# EVK-IRIS-W1-MUCLINK.net
KiCad netlist of a schematic drawn in Altium Designer
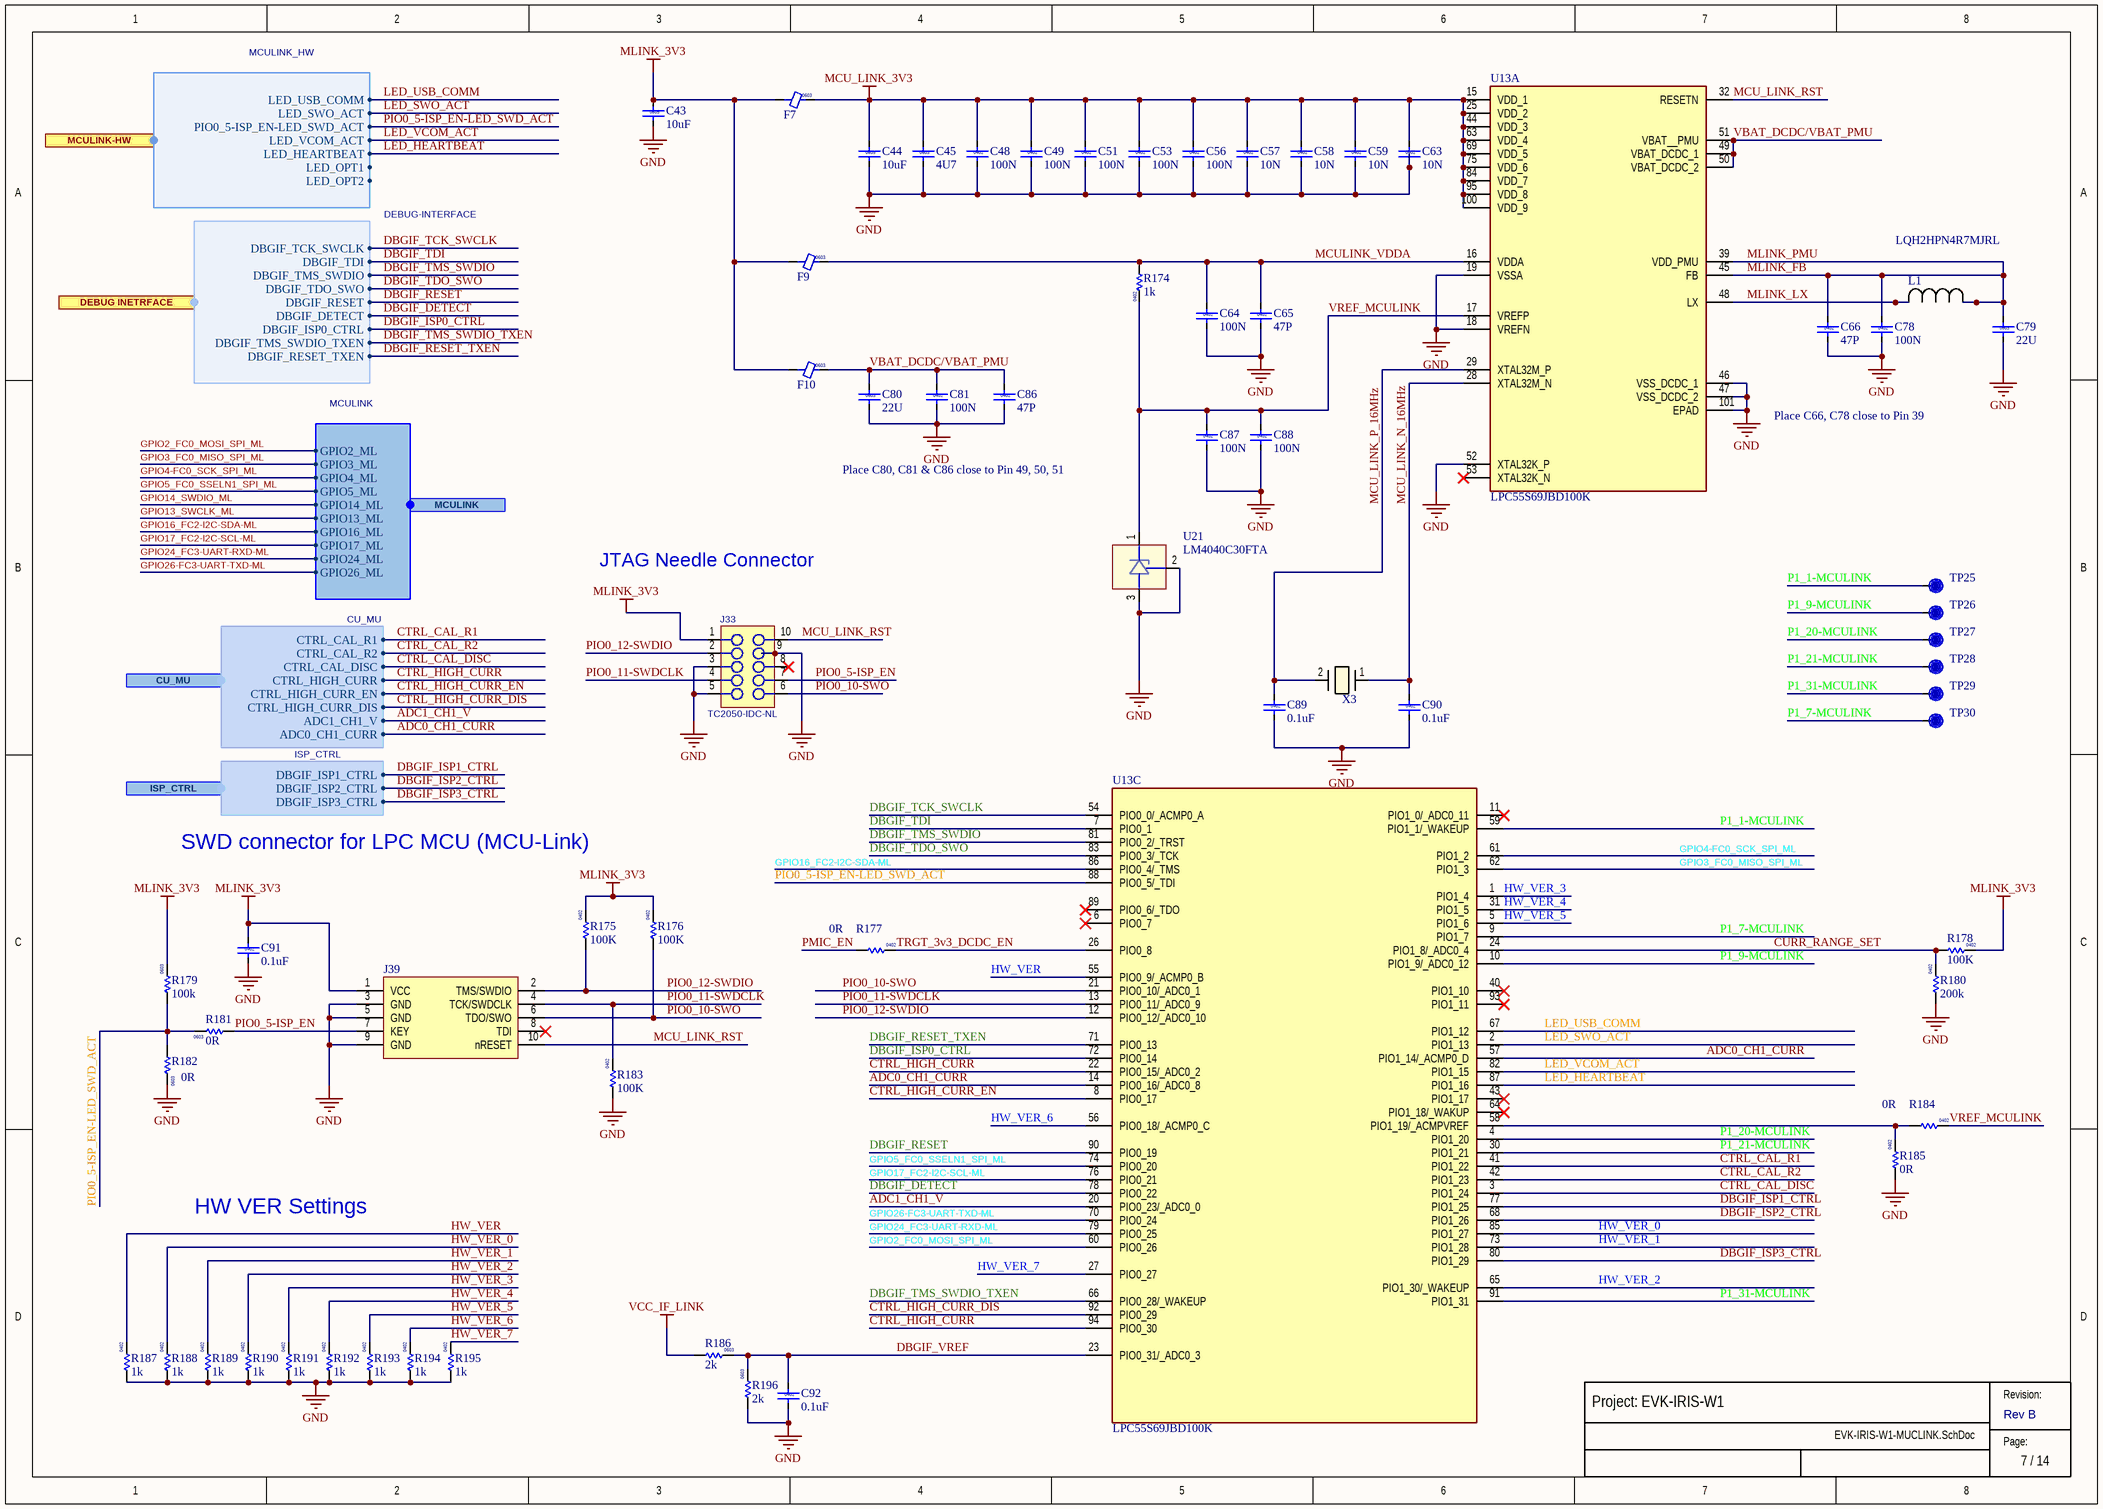
[diagram p0: EVK-IRIS-W1-MUCLINK.SchDoc]

(export (version "E")
  (design (tool "Eeschema 10.0.6"))
  (components
    (comp (ref "C43")
      (value "10uF")
      (footprint "Cap 0805 HD")
      (description "CAP CER 10uF 25V 10% X5R 0805")
      (fields
        (field (name "SIZE") "0805")
        (field (name "PART NUMBER") "120-00129")
        (field (name "TOLERANCE") "+/- 10%")
      )
      (libsource (lib "Arena_Parts_DB_Lib") (part "Cap Chip"))
    )
    (comp (ref "C44")
      (value "10uF")
      (footprint "Cap 0805 HD")
      (description "CAP CER 10uF 25V 10% X5R 0805")
      (fields
        (field (name "SIZE") "0805")
        (field (name "PART NUMBER") "120-00129")
        (field (name "TOLERANCE") "+/- 10%")
      )
      (libsource (lib "Arena_Parts_DB_Lib") (part "Cap Chip"))
    )
    (comp (ref "C45")
      (value "4U7")
      (footprint "Cap 0603 HD")
      (description "CAP CER X6S 0603 AUTOMOTIVE 4U7 10%")
      (fields
        (field (name "SIZE") "0603")
        (field (name "PART NUMBER") "UBXH01-0000278")
        (field (name "TOLERANCE") "10%")
        (field (name "EDITOR") "philippe.largier")
        (field (name "RELEASED BY") "alvaro.nussbaum")
      )
      (libsource (lib "UBX_Parts_DB_Lib") (part "Cap Chip"))
    )
    (comp (ref "C48")
      (value "100N")
      (footprint "Cap_0402_1100Lx600Wx600H_600x600Pad_350G_FLX")
      (description "CAP CER X7R 0402 100N 10% 16V")
      (fields
        (field (name "SIZE") "0402")
        (field (name "PART NUMBER") "UBXH01-0000233")
        (field (name "TOLERANCE") "10%")
        (field (name "EDITOR") "philippe.largier")
        (field (name "RELEASED BY") "charlotte.biber")
      )
      (libsource (lib "UBX_Parts_DB_Lib") (part "Cap Chip"))
    )
    (comp (ref "C49")
      (value "100N")
      (footprint "Cap_0402_1100Lx600Wx600H_600x600Pad_350G_FLX")
      (description "CAP CER X7R 0402 100N 10% 16V")
      (fields
        (field (name "SIZE") "0402")
        (field (name "PART NUMBER") "UBXH01-0000233")
        (field (name "TOLERANCE") "10%")
        (field (name "EDITOR") "philippe.largier")
        (field (name "RELEASED BY") "charlotte.biber")
      )
      (libsource (lib "UBX_Parts_DB_Lib") (part "Cap Chip"))
    )
    (comp (ref "C51")
      (value "100N")
      (footprint "Cap_0402_1100Lx600Wx600H_600x600Pad_350G_FLX")
      (description "CAP CER X7R 0402 100N 10% 16V")
      (fields
        (field (name "SIZE") "0402")
        (field (name "PART NUMBER") "UBXH01-0000233")
        (field (name "TOLERANCE") "10%")
        (field (name "EDITOR") "philippe.largier")
        (field (name "RELEASED BY") "charlotte.biber")
      )
      (libsource (lib "UBX_Parts_DB_Lib") (part "Cap Chip"))
    )
    (comp (ref "C53")
      (value "100N")
      (footprint "Cap_0402_1100Lx600Wx600H_600x600Pad_350G_FLX")
      (description "CAP CER X7R 0402 100N 10% 16V")
      (fields
        (field (name "SIZE") "0402")
        (field (name "PART NUMBER") "UBXH01-0000233")
        (field (name "TOLERANCE") "10%")
        (field (name "EDITOR") "philippe.largier")
        (field (name "RELEASED BY") "charlotte.biber")
      )
      (libsource (lib "UBX_Parts_DB_Lib") (part "Cap Chip"))
    )
    (comp (ref "C56")
      (value "100N")
      (footprint "Cap_0402_1100Lx600Wx600H_600x600Pad_350G_FLX")
      (description "CAP CER X7R 0402 100N 10% 16V")
      (fields
        (field (name "SIZE") "0402")
        (field (name "PART NUMBER") "UBXH01-0000233")
        (field (name "TOLERANCE") "10%")
        (field (name "EDITOR") "philippe.largier")
        (field (name "RELEASED BY") "charlotte.biber")
      )
      (libsource (lib "UBX_Parts_DB_Lib") (part "Cap Chip"))
    )
    (comp (ref "C57")
      (value "10N")
      (footprint "Cap_0402_1100Lx600Wx600H_600x600Pad_350G_FLX")
      (description "CAP CER X7R 0402 10N 10% 16V")
      (fields
        (field (name "SIZE") "0402")
        (field (name "PART NUMBER") "UBXH01-0023025")
        (field (name "TOLERANCE") "10%")
        (field (name "EDITOR") "roland.rust")
        (field (name "RELEASED BY") "anthony.gergis")
      )
      (libsource (lib "UBX_Parts_DB_Lib") (part "Cap Chip"))
    )
    (comp (ref "C58")
      (value "10N")
      (footprint "Cap_0402_1100Lx600Wx600H_600x600Pad_350G_FLX")
      (description "CAP CER X7R 0402 10N 10% 16V")
      (fields
        (field (name "SIZE") "0402")
        (field (name "PART NUMBER") "UBXH01-0023025")
        (field (name "TOLERANCE") "10%")
        (field (name "EDITOR") "roland.rust")
        (field (name "RELEASED BY") "anthony.gergis")
      )
      (libsource (lib "UBX_Parts_DB_Lib") (part "Cap Chip"))
    )
    (comp (ref "C59")
      (value "10N")
      (footprint "Cap_0402_1100Lx600Wx600H_600x600Pad_350G_FLX")
      (description "CAP CER X7R 0402 10N 10% 16V")
      (fields
        (field (name "SIZE") "0402")
        (field (name "PART NUMBER") "UBXH01-0023025")
        (field (name "TOLERANCE") "10%")
        (field (name "EDITOR") "roland.rust")
        (field (name "RELEASED BY") "anthony.gergis")
      )
      (libsource (lib "UBX_Parts_DB_Lib") (part "Cap Chip"))
    )
    (comp (ref "C63")
      (value "10N")
      (footprint "Cap_0402_1100Lx600Wx600H_600x600Pad_350G_FLX")
      (description "CAP CER X7R 0402 10N 10% 16V")
      (fields
        (field (name "SIZE") "0402")
        (field (name "PART NUMBER") "UBXH01-0023025")
        (field (name "TOLERANCE") "10%")
        (field (name "EDITOR") "roland.rust")
        (field (name "RELEASED BY") "anthony.gergis")
      )
      (libsource (lib "UBX_Parts_DB_Lib") (part "Cap Chip"))
    )
    (comp (ref "C64")
      (value "100N")
      (footprint "Cap_0402_1100Lx600Wx600H_600x600Pad_350G_FLX")
      (description "CAP CER X7R 0402 100N 10% 16V")
      (fields
        (field (name "SIZE") "0402")
        (field (name "PART NUMBER") "UBXH01-0000233")
        (field (name "TOLERANCE") "10%")
        (field (name "EDITOR") "philippe.largier")
        (field (name "RELEASED BY") "charlotte.biber")
      )
      (libsource (lib "UBX_Parts_DB_Lib") (part "Cap Chip"))
    )
    (comp (ref "C65")
      (value "47P")
      (footprint "Cap_0402_1100Lx600Wx600H_600x600Pad_350G_FLX")
      (description "CAP CER C0G 0402 47P 10% 25V")
      (fields
        (field (name "SIZE") "0402")
        (field (name "PART NUMBER") "UBXH01-0008022")
        (field (name "TOLERANCE") "10%")
        (field (name "EDITOR") "andreas.thiel")
      )
      (libsource (lib "UBX_Parts_DB_Lib") (part "Cap Chip"))
    )
    (comp (ref "C66")
      (value "47P")
      (footprint "Cap_0402_1100Lx600Wx600H_600x600Pad_350G_FLX")
      (description "CAP CER C0G 0402 47P 10% 25V")
      (fields
        (field (name "SIZE") "0402")
        (field (name "PART NUMBER") "UBXH01-0008022")
        (field (name "TOLERANCE") "10%")
        (field (name "EDITOR") "andreas.thiel")
      )
      (libsource (lib "UBX_Parts_DB_Lib") (part "Cap Chip"))
    )
    (comp (ref "C78")
      (value "100N")
      (footprint "Cap_0402_1100Lx600Wx600H_600x600Pad_350G_FLX")
      (description "CAP CER X7R 0402 100N 10% 16V")
      (fields
        (field (name "SIZE") "0402")
        (field (name "PART NUMBER") "UBXH01-0000233")
        (field (name "TOLERANCE") "10%")
        (field (name "EDITOR") "philippe.largier")
        (field (name "RELEASED BY") "charlotte.biber")
      )
      (libsource (lib "UBX_Parts_DB_Lib") (part "Cap Chip"))
    )
    (comp (ref "C79")
      (value "22U")
      (footprint "Cap 0603")
      (description "CAP CER X5R 0603 22U 20% 10V")
      (fields
        (field (name "SIZE") "0603")
        (field (name "PART NUMBER") "UBXH01-0000150")
        (field (name "TOLERANCE") "20%")
        (field (name "EDITOR") "dario.antonaz")
        (field (name "RELEASED BY") "pasquale.scorca")
      )
      (libsource (lib "UBX_Parts_DB_Lib") (part "Cap Chip"))
    )
    (comp (ref "C80")
      (value "22U")
      (footprint "Cap 0603")
      (description "CAP CER X5R 0603 22U 20% 10V")
      (fields
        (field (name "SIZE") "0603")
        (field (name "PART NUMBER") "UBXH01-0000150")
        (field (name "TOLERANCE") "20%")
        (field (name "EDITOR") "dario.antonaz")
        (field (name "RELEASED BY") "pasquale.scorca")
      )
      (libsource (lib "UBX_Parts_DB_Lib") (part "Cap Chip"))
    )
    (comp (ref "C81")
      (value "100N")
      (footprint "Cap_0402_1100Lx600Wx600H_600x600Pad_350G_FLX")
      (description "CAP CER X7R 0402 100N 10% 16V")
      (fields
        (field (name "SIZE") "0402")
        (field (name "PART NUMBER") "UBXH01-0000233")
        (field (name "TOLERANCE") "10%")
        (field (name "EDITOR") "philippe.largier")
        (field (name "RELEASED BY") "charlotte.biber")
      )
      (libsource (lib "UBX_Parts_DB_Lib") (part "Cap Chip"))
    )
    (comp (ref "C86")
      (value "47P")
      (footprint "Cap_0402_1100Lx600Wx600H_600x600Pad_350G_FLX")
      (description "CAP CER C0G 0402 47P 10% 25V")
      (fields
        (field (name "SIZE") "0402")
        (field (name "PART NUMBER") "UBXH01-0008022")
        (field (name "TOLERANCE") "10%")
        (field (name "EDITOR") "andreas.thiel")
      )
      (libsource (lib "UBX_Parts_DB_Lib") (part "Cap Chip"))
    )
    (comp (ref "C87")
      (value "100N")
      (footprint "Cap_0402_1100Lx600Wx600H_600x600Pad_350G_FLX")
      (description "CAP CER X7R 0402 100N 10% 16V")
      (fields
        (field (name "SIZE") "0402")
        (field (name "PART NUMBER") "UBXH01-0000233")
        (field (name "TOLERANCE") "10%")
        (field (name "EDITOR") "philippe.largier")
        (field (name "RELEASED BY") "charlotte.biber")
      )
      (libsource (lib "UBX_Parts_DB_Lib") (part "Cap Chip"))
    )
    (comp (ref "C88")
      (value "100N")
      (footprint "Cap_0402_1100Lx600Wx600H_600x600Pad_350G_FLX")
      (description "CAP CER X7R 0402 100N 10% 16V")
      (fields
        (field (name "SIZE") "0402")
        (field (name "PART NUMBER") "UBXH01-0000233")
        (field (name "TOLERANCE") "10%")
        (field (name "EDITOR") "philippe.largier")
        (field (name "RELEASED BY") "charlotte.biber")
      )
      (libsource (lib "UBX_Parts_DB_Lib") (part "Cap Chip"))
    )
    (comp (ref "C89")
      (value "0.1uF")
      (footprint "Cap 0402 HD")
      (description "Cap, Ceramic 0.1uF 10V 10% X5R 0402")
      (fields
        (field (name "SIZE") "0402")
        (field (name "PART NUMBER") "120-00016")
        (field (name "TOLERANCE") "+/- 10%")
      )
      (libsource (lib "Arena_Parts_DB_Lib") (part "Cap Chip"))
    )
    (comp (ref "C90")
      (value "0.1uF")
      (footprint "Cap 0402 HD")
      (description "Cap, Ceramic 0.1uF 10V 10% X5R 0402")
      (fields
        (field (name "SIZE") "0402")
        (field (name "PART NUMBER") "120-00016")
        (field (name "TOLERANCE") "+/- 10%")
      )
      (libsource (lib "Arena_Parts_DB_Lib") (part "Cap Chip"))
    )
    (comp (ref "C91")
      (value "0.1uF")
      (footprint "Cap 0402 HD")
      (description "Cap, Ceramic 0.1uF 10V 10% X5R 0402")
      (fields
        (field (name "SIZE") "0402")
        (field (name "PART NUMBER") "120-00016")
        (field (name "TOLERANCE") "+/- 10%")
      )
      (libsource (lib "Arena_Parts_DB_Lib") (part "Cap Chip"))
    )
    (comp (ref "C92")
      (value "0.1uF")
      (footprint "Cap 0402 HD")
      (description "Cap, Ceramic 0.1uF 10V 10% X5R 0402")
      (fields
        (field (name "SIZE") "0402")
        (field (name "PART NUMBER") "120-00016")
        (field (name "TOLERANCE") "+/- 10%")
      )
      (libsource (lib "Arena_Parts_DB_Lib") (part "Cap Chip"))
    )
    (comp (ref "F7")
      (value "UBXH08-0041002")
      (footprint "IND 0603")
      (description "FERRITE BEAD MURATA BLM18HD 0603 600R@100MHZ")
      (fields
        (field (name "SIZE") "0603")
        (field (name "MANUFACTURER") "Murata Manufacturing Company, Ltd.")
        (field (name "EDITOR") "roland.rust")
        (field (name "RELEASED BY") "roland.rust")
      )
      (libsource (lib "UBX_Parts_DB_Lib") (part "FB sm"))
    )
    (comp (ref "F9")
      (value "UBXH08-0041002")
      (footprint "IND 0603")
      (description "FERRITE BEAD MURATA BLM18HD 0603 600R@100MHZ")
      (fields
        (field (name "SIZE") "0603")
        (field (name "MANUFACTURER") "Murata Manufacturing Company, Ltd.")
        (field (name "EDITOR") "roland.rust")
        (field (name "RELEASED BY") "roland.rust")
      )
      (libsource (lib "UBX_Parts_DB_Lib") (part "FB sm"))
    )
    (comp (ref "F10")
      (value "UBXH08-0041002")
      (footprint "IND 0603")
      (description "FERRITE BEAD MURATA BLM18HD 0603 600R@100MHZ")
      (fields
        (field (name "SIZE") "0603")
        (field (name "MANUFACTURER") "Murata Manufacturing Company, Ltd.")
        (field (name "EDITOR") "roland.rust")
        (field (name "RELEASED BY") "roland.rust")
      )
      (libsource (lib "UBX_Parts_DB_Lib") (part "FB sm"))
    )
    (comp (ref "J33")
      (value "TC2050-IDC-NLDNP")
      (footprint "TC2050-IDC-NL")
      (description "CON PADS FOR CBL PLUG-OF-NAILS 10-PIN NO LEGS")
      (fields
        (field (name "MANUFACTURER P/N") "TC2050-IDC-NL")
        (field (name "PART NUMBER") "TC2050-IDC-NL")
        (field (name "MANUFACTURER") "TAG Connect")
        (field (name "ADDED BY") "Paul B")
      )
      (libsource (lib "LEGACY_Rigado_AltiumLib") (part "CON-10Pin_2Row_ALT"))
    )
    (comp (ref "J39")
      (value "130-00099")
      (footprint "HDR.050P-10Pin-2x5-SMT_Key")
      (description "Header 0.05\" 10Pin 2Row SMD Black")
      (fields (field (name "VOLTAGE") "None"))
      (libsource (lib "Arena_Parts_DB_Lib") (part "JTAG-10Pin"))
    )
    (comp (ref "L1")
      (value "LQH2HPN4R7MJRL")
      (footprint "IND_LQH2HPN4R7MJRL_MUR")
      (description "No Description Available")
      (fields (field (name "COPYRIGHT") "Copyright (C) 2023 Ultra Librarian. All rights reserved."))
      (libsource (lib "LQH2HPN4R7MJRL") (part "LQH2HPN4R7MJRL"))
    )
    (comp (ref "R174")
      (value "1k")
      (footprint "RES 0402 HD")
      (description "Resistor 1k ohm 1% 1/16W, 0402")
      (fields
        (field (name "SIZE") "0402")
        (field (name "PART NUMBER") "180-00021")
        (field (name "POWER") "1/16W")
      )
      (libsource (lib "Arena_Parts_DB_Lib") (part "Res sm"))
    )
    (comp (ref "R175")
      (value "100K")
      (footprint "RES 0402 HD")
      (description "RES THICK FILM CHIP 0402 100K 1% 63mW")
      (fields
        (field (name "SIZE") "0402")
        (field (name "PART NUMBER") "UBXH18-0000005")
        (field (name "TOLERANCE") "1%")
        (field (name "EDITOR") "dario.antonaz")
        (field (name "RELEASED BY") "sandro.sestan")
      )
      (libsource (lib "UBX_Parts_DB_Lib") (part "Res sm"))
    )
    (comp (ref "R176")
      (value "100K")
      (footprint "RES 0402 HD")
      (description "RES THICK FILM CHIP 0402 100K 1% 63mW")
      (fields
        (field (name "SIZE") "0402")
        (field (name "PART NUMBER") "UBXH18-0000005")
        (field (name "TOLERANCE") "1%")
        (field (name "EDITOR") "dario.antonaz")
        (field (name "RELEASED BY") "sandro.sestan")
      )
      (libsource (lib "UBX_Parts_DB_Lib") (part "Res sm"))
    )
    (comp (ref "R177")
      (value "0R")
      (footprint "RES 0402 HD")
      (description "RES THICK FILM CHIP 0402 0R 0 100mW")
      (fields
        (field (name "SIZE") "0402")
        (field (name "PART NUMBER") "UBXH18-0003002")
        (field (name "TOLERANCE") "0")
        (field (name "EDITOR") "charlotte.biber")
        (field (name "RELEASED BY") "peter.mueller")
      )
      (libsource (lib "UBX_Parts_DB_Lib") (part "Res sm"))
    )
    (comp (ref "R178")
      (value "100K")
      (footprint "RES 0402 HD")
      (description "RES THICK FILM CHIP 0402 100K 1% 63mW")
      (fields
        (field (name "SIZE") "0402")
        (field (name "PART NUMBER") "UBXH18-0000005")
        (field (name "TOLERANCE") "1%")
        (field (name "EDITOR") "dario.antonaz")
        (field (name "RELEASED BY") "sandro.sestan")
      )
      (libsource (lib "UBX_Parts_DB_Lib") (part "Res sm"))
    )
    (comp (ref "R179")
      (value "100k")
      (footprint "RES 0603 HD")
      (description "Resistor, 100k ohm 1% 1/10W, 0603")
      (fields
        (field (name "SIZE") "0603")
        (field (name "PART NUMBER") "180-00014")
        (field (name "POWER") "1/10W")
      )
      (libsource (lib "Arena_Parts_DB_Lib") (part "Res sm"))
    )
    (comp (ref "R180")
      (value "200k")
      (footprint "RES 0402 HD")
      (description "Resistor 200k ohm 1%, 1/16W, 0402")
      (fields
        (field (name "SIZE") "0402")
        (field (name "PART NUMBER") "180-00055")
        (field (name "POWER") "1/16W")
      )
      (libsource (lib "Arena_Parts_DB_Lib") (part "Res sm"))
    )
    (comp (ref "R181")
      (value "0R")
      (footprint "RES 0603 HD")
      (description "RES THICK FILM CHIP 0603 0R 0 100mW")
      (fields
        (field (name "SIZE") "0603")
        (field (name "PART NUMBER") "UBXH18-0003001")
        (field (name "TOLERANCE") "0")
        (field (name "EDITOR") "martin.frauchiger")
        (field (name "RELEASED BY") "martin.frauchiger")
      )
      (libsource (lib "UBX_Parts_DB_Lib") (part "Res sm"))
    )
    (comp (ref "R182")
      (value "0R")
      (footprint "RES 0603 HD")
      (description "Resistor 0 ohm Jumper, 1/10W, 0603")
      (fields
        (field (name "SIZE") "0603")
        (field (name "PART NUMBER") "180-00012")
        (field (name "POWER") "1/10W")
      )
      (libsource (lib "Arena_Parts_DB_Lib") (part "Res sm"))
    )
    (comp (ref "R183")
      (value "100K")
      (footprint "RES 0402 HD")
      (description "RES THICK FILM CHIP 0402 100K 1% 63mW")
      (fields
        (field (name "SIZE") "0402")
        (field (name "PART NUMBER") "UBXH18-0000005")
        (field (name "TOLERANCE") "1%")
        (field (name "EDITOR") "dario.antonaz")
        (field (name "RELEASED BY") "sandro.sestan")
      )
      (libsource (lib "UBX_Parts_DB_Lib") (part "Res sm"))
    )
    (comp (ref "R184")
      (value "0R")
      (footprint "RES 0402 HD")
      (description "RES THICK FILM CHIP 0402 0R 0 100mW")
      (fields
        (field (name "SIZE") "0402")
        (field (name "PART NUMBER") "UBXH18-0003002")
        (field (name "TOLERANCE") "0")
        (field (name "EDITOR") "charlotte.biber")
        (field (name "RELEASED BY") "peter.mueller")
      )
      (libsource (lib "UBX_Parts_DB_Lib") (part "Res sm"))
    )
    (comp (ref "R185")
      (value "0R")
      (footprint "RES 0402 HD")
      (description "RES THICK FILM CHIP 0402 0R 0 100mW")
      (fields
        (field (name "SIZE") "0402")
        (field (name "PART NUMBER") "UBXH18-0003002")
        (field (name "TOLERANCE") "0")
        (field (name "EDITOR") "charlotte.biber")
        (field (name "RELEASED BY") "peter.mueller")
      )
      (libsource (lib "UBX_Parts_DB_Lib") (part "Res sm"))
    )
    (comp (ref "R186")
      (value "2k")
      (footprint "RES 0603 HD")
      (description "Resistor 2k ohm 1% 1/10W, 0603.")
      (fields
        (field (name "SIZE") "0603")
        (field (name "PART NUMBER") "180-00037")
        (field (name "POWER") "1/10W")
      )
      (libsource (lib "Arena_Parts_DB_Lib") (part "Res sm"))
    )
    (comp (ref "R187")
      (value "1k")
      (footprint "RES 0402 HD")
      (description "Resistor 1k ohm 1% 1/16W, 0402")
      (fields
        (field (name "SIZE") "0402")
        (field (name "PART NUMBER") "180-00021")
        (field (name "POWER") "1/16W")
      )
      (libsource (lib "Arena_Parts_DB_Lib") (part "Res sm"))
    )
    (comp (ref "R188")
      (value "1k")
      (footprint "RES 0402 HD")
      (description "Resistor 1k ohm 1% 1/16W, 0402")
      (fields
        (field (name "SIZE") "0402")
        (field (name "PART NUMBER") "180-00021")
        (field (name "POWER") "1/16W")
      )
      (libsource (lib "Arena_Parts_DB_Lib") (part "Res sm"))
    )
    (comp (ref "R189")
      (value "1k")
      (footprint "RES 0402 HD")
      (description "Resistor 1k ohm 1% 1/16W, 0402")
      (fields
        (field (name "SIZE") "0402")
        (field (name "PART NUMBER") "180-00021")
        (field (name "POWER") "1/16W")
      )
      (libsource (lib "Arena_Parts_DB_Lib") (part "Res sm"))
    )
    (comp (ref "R190")
      (value "1k")
      (footprint "RES 0402 HD")
      (description "Resistor 1k ohm 1% 1/16W, 0402")
      (fields
        (field (name "SIZE") "0402")
        (field (name "PART NUMBER") "180-00021")
        (field (name "POWER") "1/16W")
      )
      (libsource (lib "Arena_Parts_DB_Lib") (part "Res sm"))
    )
    (comp (ref "R191")
      (value "1k")
      (footprint "RES 0402 HD")
      (description "Resistor 1k ohm 1% 1/16W, 0402")
      (fields
        (field (name "SIZE") "0402")
        (field (name "PART NUMBER") "180-00021")
        (field (name "POWER") "1/16W")
      )
      (libsource (lib "Arena_Parts_DB_Lib") (part "Res sm"))
    )
    (comp (ref "R192")
      (value "1k")
      (footprint "RES 0402 HD")
      (description "Resistor 1k ohm 1% 1/16W, 0402")
      (fields
        (field (name "SIZE") "0402")
        (field (name "PART NUMBER") "180-00021")
        (field (name "POWER") "1/16W")
      )
      (libsource (lib "Arena_Parts_DB_Lib") (part "Res sm"))
    )
    (comp (ref "R193")
      (value "1k")
      (footprint "RES 0402 HD")
      (description "Resistor 1k ohm 1% 1/16W, 0402")
      (fields
        (field (name "SIZE") "0402")
        (field (name "PART NUMBER") "180-00021")
        (field (name "POWER") "1/16W")
      )
      (libsource (lib "Arena_Parts_DB_Lib") (part "Res sm"))
    )
    (comp (ref "R194")
      (value "1k")
      (footprint "RES 0402 HD")
      (description "Resistor 1k ohm 1% 1/16W, 0402")
      (fields
        (field (name "SIZE") "0402")
        (field (name "PART NUMBER") "180-00021")
        (field (name "POWER") "1/16W")
      )
      (libsource (lib "Arena_Parts_DB_Lib") (part "Res sm"))
    )
    (comp (ref "R195")
      (value "1k")
      (footprint "RES 0402 HD")
      (description "Resistor 1k ohm 1% 1/16W, 0402")
      (fields
        (field (name "SIZE") "0402")
        (field (name "PART NUMBER") "180-00021")
        (field (name "POWER") "1/16W")
      )
      (libsource (lib "Arena_Parts_DB_Lib") (part "Res sm"))
    )
    (comp (ref "R196")
      (value "2k")
      (footprint "RES 0603 HD")
      (description "Resistor 2k ohm 1% 1/10W, 0603.")
      (fields
        (field (name "SIZE") "0603")
        (field (name "PART NUMBER") "180-00037")
        (field (name "POWER") "1/10W")
      )
      (libsource (lib "Arena_Parts_DB_Lib") (part "Res sm"))
    )
    (comp (ref "TP25")
      (value "TP")
      (footprint "TP10R")
      (description "Testpoint, Round 1.0mm Dia")
      (fields
        (field (name "PART NUMBER") "TP10R")
        (field (name "ADDED BY") "Jeremy D")
        (field (name "CHECKED BY") "Paul B")
      )
      (libsource (lib "LEGACY_Rigado_AltiumLib") (part "TP_R"))
    )
    (comp (ref "TP26")
      (value "TP")
      (footprint "TP10R")
      (description "Testpoint, Round 1.0mm Dia")
      (fields
        (field (name "PART NUMBER") "TP10R")
        (field (name "ADDED BY") "Jeremy D")
        (field (name "CHECKED BY") "Paul B")
      )
      (libsource (lib "LEGACY_Rigado_AltiumLib") (part "TP_R"))
    )
    (comp (ref "TP27")
      (value "TP")
      (footprint "TP10R")
      (description "Testpoint, Round 1.0mm Dia")
      (fields
        (field (name "PART NUMBER") "TP10R")
        (field (name "ADDED BY") "Jeremy D")
        (field (name "CHECKED BY") "Paul B")
      )
      (libsource (lib "LEGACY_Rigado_AltiumLib") (part "TP_R"))
    )
    (comp (ref "TP28")
      (value "TP")
      (footprint "TP10R")
      (description "Testpoint, Round 1.0mm Dia")
      (fields
        (field (name "PART NUMBER") "TP10R")
        (field (name "ADDED BY") "Jeremy D")
        (field (name "CHECKED BY") "Paul B")
      )
      (libsource (lib "LEGACY_Rigado_AltiumLib") (part "TP_R"))
    )
    (comp (ref "TP29")
      (value "TP")
      (footprint "TP10R")
      (description "Testpoint, Round 1.0mm Dia")
      (fields
        (field (name "PART NUMBER") "TP10R")
        (field (name "ADDED BY") "Jeremy D")
        (field (name "CHECKED BY") "Paul B")
      )
      (libsource (lib "LEGACY_Rigado_AltiumLib") (part "TP_R"))
    )
    (comp (ref "TP30")
      (value "TP")
      (footprint "TP10R")
      (description "Testpoint, Round 1.0mm Dia")
      (fields
        (field (name "PART NUMBER") "TP10R")
        (field (name "ADDED BY") "Jeremy D")
        (field (name "CHECKED BY") "Paul B")
      )
      (libsource (lib "LEGACY_Rigado_AltiumLib") (part "TP_R"))
    )
    (comp (ref "U13")
      (value "LPC55S69JBD100K")
      (footprint "QFP50P1600X1600X160-101N")
      (description "NXP - LPC55S69JBD100K - MCU, 32BIT, 100MHZ, HLQFP")
      (fields (field (name "MOUSER PART NUMBER") "771-LPC55S69JBD100K"))
      (libsource (lib "LPC55S69JBD100K") (part "LPC55S69JBD100K"))
    )
    (comp (ref "U21")
      (value "LM4040C30FTA")
      (footprint "SOT-23")
      (description "Shunt Voltage Reference IC Fixed 3V V ±0.5% 15 mA SOT-23-3")
      (libsource (lib "LM4040C30FTA") (part "LM4040C30FTA"))
    )
    (comp (ref "X3")
      (value "CX3225GA16000D0PTVCC")
      (footprint "xtal2_CX3225GA_AVX")
      (description "No Description Available")
      (fields (field (name "COPYRIGHT") "Copyright (C) 2023 Ultra Librarian. All rights reserved."))
      (libsource (lib "CX3225GA16000D0PTVCC") (part "CX3225GA16000D0PTVCC"))
    )
  )
  (nets
    (net (code "6") (name "/ADC0_CH1_CURR") (class "Default")
      (node (ref "U13") (pin "14") (pinfunction "PIO0_16/_ADC0_8_14") (pintype "passive"))
      (node (ref "U13") (pin "57") (pinfunction "PIO1_14/_ACMP0_D_57") (pintype "passive"))
    )
    (net (code "7") (name "/ADC1_CH1_V") (class "Default")
      (node (ref "U13") (pin "20") (pinfunction "PIO0_23/_ADC0_0_20") (pintype "passive"))
    )
    (net (code "8") (name "/CTRL_CAL_DISC") (class "Default")
      (node (ref "U13") (pin "3") (pinfunction "PIO1_24_3") (pintype "passive"))
    )
    (net (code "9") (name "/CTRL_CAL_R1") (class "Default")
      (node (ref "U13") (pin "41") (pinfunction "PIO1_22_41") (pintype "passive"))
    )
    (net (code "10") (name "/CTRL_CAL_R2") (class "Default")
      (node (ref "U13") (pin "42") (pinfunction "PIO1_23_42") (pintype "passive"))
    )
    (net (code "11") (name "/CTRL_HIGH_CURR") (class "Default")
      (node (ref "U13") (pin "22") (pinfunction "PIO0_15/_ADC0_2_22") (pintype "passive"))
      (node (ref "U13") (pin "94") (pinfunction "PIO0_30_94") (pintype "passive"))
    )
    (net (code "12") (name "/CTRL_HIGH_CURR_DIS") (class "Default")
      (node (ref "U13") (pin "92") (pinfunction "PIO0_29_92") (pintype "passive"))
    )
    (net (code "13") (name "/CTRL_HIGH_CURR_EN") (class "Default")
      (node (ref "U13") (pin "8") (pinfunction "PIO0_17_8") (pintype "passive"))
    )
    (net (code "14") (name "/CURR_RANGE_SET") (class "Default")
      (node (ref "R178") (pin "1") (pinfunction "1_1") (pintype "passive"))
      (node (ref "R180") (pin "2") (pinfunction "2_2") (pintype "passive"))
      (node (ref "U13") (pin "24") (pinfunction "PIO1_8/_ADC0_4_24") (pintype "passive"))
    )
    (net (code "15") (name "/DBGIF_DETECT") (class "Default")
      (node (ref "U13") (pin "78") (pinfunction "PIO0_22_78") (pintype "passive"))
    )
    (net (code "16") (name "/DBGIF_ISP0_CTRL") (class "Default")
      (node (ref "U13") (pin "72") (pinfunction "PIO0_14_72") (pintype "passive"))
    )
    (net (code "17") (name "/DBGIF_ISP1_CTRL") (class "Default")
      (node (ref "U13") (pin "77") (pinfunction "PIO1_25_77") (pintype "passive"))
    )
    (net (code "18") (name "/DBGIF_ISP2_CTRL") (class "Default")
      (node (ref "U13") (pin "68") (pinfunction "PIO1_26_68") (pintype "passive"))
    )
    (net (code "19") (name "/DBGIF_ISP3_CTRL") (class "Default")
      (node (ref "U13") (pin "80") (pinfunction "PIO1_29_80") (pintype "passive"))
    )
    (net (code "20") (name "/DBGIF_RESET") (class "Default")
      (node (ref "U13") (pin "90") (pinfunction "PIO0_19_90") (pintype "passive"))
    )
    (net (code "21") (name "/DBGIF_RESET_TXEN") (class "Default")
      (node (ref "U13") (pin "71") (pinfunction "PIO0_13_71") (pintype "passive"))
    )
    (net (code "22") (name "/DBGIF_TCK_SWCLK") (class "Default")
      (node (ref "U13") (pin "54") (pinfunction "PIO0_0/_ACMP0_A_54") (pintype "passive"))
    )
    (net (code "23") (name "/DBGIF_TDI") (class "Default")
      (node (ref "U13") (pin "7") (pinfunction "PIO0_1_7") (pintype "passive"))
    )
    (net (code "24") (name "/DBGIF_TDO_SWO") (class "Default")
      (node (ref "U13") (pin "83") (pinfunction "PIO0_3/_TCK_83") (pintype "passive"))
    )
    (net (code "25") (name "/DBGIF_TMS_SWDIO") (class "Default")
      (node (ref "U13") (pin "81") (pinfunction "PIO0_2/_TRST_81") (pintype "passive"))
    )
    (net (code "26") (name "/DBGIF_TMS_SWDIO_TXEN") (class "Default")
      (node (ref "U13") (pin "66") (pinfunction "PIO0_28/_WAKEUP_66") (pintype "passive"))
    )
    (net (code "27") (name "/DBGIF_VREF") (class "Default")
      (node (ref "C92") (pin "1") (pinfunction "1_1") (pintype "passive"))
      (node (ref "R186") (pin "2") (pinfunction "2_2") (pintype "passive"))
      (node (ref "R196") (pin "2") (pinfunction "2_2") (pintype "passive"))
      (node (ref "U13") (pin "23") (pinfunction "PIO0_31/_ADC0_3_23") (pintype "passive"))
    )
    (net (code "28") (name "/GPIO2_FC0_MOSI_SPI_ML") (class "Default")
      (node (ref "U13") (pin "60") (pinfunction "PIO0_26_60") (pintype "passive"))
    )
    (net (code "29") (name "/GPIO3_FC0_MISO_SPI_ML") (class "Default")
      (node (ref "U13") (pin "62") (pinfunction "PIO1_3_62") (pintype "passive"))
    )
    (net (code "30") (name "/GPIO4-FC0_SCK_SPI_ML") (class "Default")
      (node (ref "U13") (pin "61") (pinfunction "PIO1_2_61") (pintype "passive"))
    )
    (net (code "31") (name "/GPIO5_FC0_SSELN1_SPI_ML") (class "Default")
      (node (ref "U13") (pin "74") (pinfunction "PIO0_20_74") (pintype "passive"))
    )
    (net (code "34") (name "/GPIO16_FC2-I2C-SDA-ML") (class "Default")
      (node (ref "U13") (pin "86") (pinfunction "PIO0_4/_TMS_86") (pintype "passive"))
    )
    (net (code "35") (name "/GPIO17_FC2-I2C-SCL-ML") (class "Default")
      (node (ref "U13") (pin "76") (pinfunction "PIO0_21_76") (pintype "passive"))
    )
    (net (code "36") (name "/GPIO24_FC3-UART-RXD-ML") (class "Default")
      (node (ref "U13") (pin "79") (pinfunction "PIO0_25_79") (pintype "passive"))
    )
    (net (code "37") (name "/GPIO26-FC3-UART-TXD-ML") (class "Default")
      (node (ref "U13") (pin "70") (pinfunction "PIO0_24_70") (pintype "passive"))
    )
    (net (code "38") (name "/HW_VER") (class "Default")
      (node (ref "R187") (pin "2") (pinfunction "2_2") (pintype "passive"))
      (node (ref "U13") (pin "55") (pinfunction "PIO0_9/_ACMP0_B_55") (pintype "passive"))
    )
    (net (code "39") (name "/HW_VER_0") (class "Default")
      (node (ref "R188") (pin "2") (pinfunction "2_2") (pintype "passive"))
      (node (ref "U13") (pin "85") (pinfunction "PIO1_27_85") (pintype "passive"))
    )
    (net (code "40") (name "/HW_VER_1") (class "Default")
      (node (ref "R189") (pin "2") (pinfunction "2_2") (pintype "passive"))
      (node (ref "U13") (pin "73") (pinfunction "PIO1_28_73") (pintype "passive"))
    )
    (net (code "41") (name "/HW_VER_2") (class "Default")
      (node (ref "R190") (pin "2") (pinfunction "2_2") (pintype "passive"))
      (node (ref "U13") (pin "65") (pinfunction "PIO1_30/_WAKEUP_65") (pintype "passive"))
    )
    (net (code "42") (name "/HW_VER_3") (class "Default")
      (node (ref "R191") (pin "2") (pinfunction "2_2") (pintype "passive"))
      (node (ref "U13") (pin "1") (pinfunction "PIO1_4_1") (pintype "passive"))
    )
    (net (code "43") (name "/HW_VER_4") (class "Default")
      (node (ref "R192") (pin "2") (pinfunction "2_2") (pintype "passive"))
      (node (ref "U13") (pin "31") (pinfunction "PIO1_5_31") (pintype "passive"))
    )
    (net (code "44") (name "/HW_VER_5") (class "Default")
      (node (ref "R193") (pin "2") (pinfunction "2_2") (pintype "passive"))
      (node (ref "U13") (pin "5") (pinfunction "PIO1_6_5") (pintype "passive"))
    )
    (net (code "45") (name "/HW_VER_6") (class "Default")
      (node (ref "R194") (pin "2") (pinfunction "2_2") (pintype "passive"))
      (node (ref "U13") (pin "56") (pinfunction "PIO0_18/_ACMP0_C_56") (pintype "passive"))
    )
    (net (code "46") (name "/HW_VER_7") (class "Default")
      (node (ref "R195") (pin "2") (pinfunction "2_2") (pintype "passive"))
      (node (ref "U13") (pin "27") (pinfunction "PIO0_27_27") (pintype "passive"))
    )
    (net (code "47") (name "/LED_HEARTBEAT") (class "Default")
      (node (ref "U13") (pin "87") (pinfunction "PIO1_16_87") (pintype "passive"))
    )
    (net (code "48") (name "/LED_SWO_ACT") (class "Default")
      (node (ref "U13") (pin "2") (pinfunction "PIO1_13_2") (pintype "passive"))
    )
    (net (code "49") (name "/LED_USB_COMM") (class "Default")
      (node (ref "U13") (pin "67") (pinfunction "PIO1_12_67") (pintype "passive"))
    )
    (net (code "50") (name "/LED_VCOM_ACT") (class "Default")
      (node (ref "U13") (pin "82") (pinfunction "PIO1_15_82") (pintype "passive"))
    )
    (net (code "51") (name "/MCULINK_VDDA") (class "Default")
      (node (ref "C64") (pin "1") (pinfunction "1_1") (pintype "passive"))
      (node (ref "C65") (pin "1") (pinfunction "1_1") (pintype "passive"))
      (node (ref "F9") (pin "2") (pinfunction "2_2") (pintype "passive"))
      (node (ref "R174") (pin "2") (pinfunction "2_2") (pintype "passive"))
      (node (ref "U13") (pin "16") (pinfunction "VDDA_16") (pintype "passive"))
    )
    (net (code "52") (name "/MCU_LINK_N_16MHz") (class "Default")
      (node (ref "C90") (pin "1") (pinfunction "1_1") (pintype "passive"))
      (node (ref "U13") (pin "28") (pinfunction "XTAL32M_N_28") (pintype "passive"))
      (node (ref "X3") (pin "1") (pinfunction "1_1") (pintype "passive"))
    )
    (net (code "53") (name "/MCU_LINK_P_16MHz") (class "Default")
      (node (ref "C89") (pin "1") (pinfunction "1_1") (pintype "passive"))
      (node (ref "U13") (pin "29") (pinfunction "XTAL32M_P_29") (pintype "passive"))
      (node (ref "X3") (pin "2") (pinfunction "2_2") (pintype "passive"))
    )
    (net (code "54") (name "/MCU_LINK_RST") (class "Default")
      (node (ref "J33") (pin "10") (pintype "passive"))
      (node (ref "J39") (pin "10") (pinfunction "nRESET_10") (pintype "passive"))
      (node (ref "U13") (pin "32") (pinfunction "RESETN_32") (pintype "passive"))
    )
    (net (code "55") (name "/MLINK_FB") (class "Default")
      (node (ref "C66") (pin "1") (pinfunction "1_1") (pintype "passive"))
      (node (ref "C78") (pin "1") (pinfunction "1_1") (pintype "passive"))
      (node (ref "C79") (pin "1") (pinfunction "1_1") (pintype "passive"))
      (node (ref "L1") (pin "1") (pinfunction "1_1") (pintype "passive"))
      (node (ref "U13") (pin "39") (pinfunction "VDD_PMU_39") (pintype "passive"))
      (node (ref "U13") (pin "45") (pinfunction "FB_45") (pintype "passive"))
    )
    (net (code "56") (name "/MLINK_LX") (class "Default")
      (node (ref "L1") (pin "2") (pinfunction "2_2") (pintype "passive"))
      (node (ref "U13") (pin "48") (pinfunction "LX_48") (pintype "passive"))
    )
    (net (code "57") (name "/P1_1-MCULINK") (class "Default")
      (node (ref "TP25") (pin "1") (pintype "passive"))
      (node (ref "U13") (pin "59") (pinfunction "PIO1_1/_WAKEUP_59") (pintype "passive"))
    )
    (net (code "58") (name "/P1_7-MCULINK") (class "Default")
      (node (ref "TP30") (pin "1") (pintype "passive"))
      (node (ref "U13") (pin "9") (pinfunction "PIO1_7_9") (pintype "passive"))
    )
    (net (code "59") (name "/P1_9-MCULINK") (class "Default")
      (node (ref "TP26") (pin "1") (pintype "passive"))
      (node (ref "U13") (pin "10") (pinfunction "PIO1_9/_ADC0_12_10") (pintype "passive"))
    )
    (net (code "60") (name "/P1_20-MCULINK") (class "Default")
      (node (ref "TP27") (pin "1") (pintype "passive"))
      (node (ref "U13") (pin "4") (pinfunction "PIO1_20_4") (pintype "passive"))
    )
    (net (code "61") (name "/P1_21-MCULINK") (class "Default")
      (node (ref "TP28") (pin "1") (pintype "passive"))
      (node (ref "U13") (pin "30") (pinfunction "PIO1_21_30") (pintype "passive"))
    )
    (net (code "62") (name "/P1_31-MCULINK") (class "Default")
      (node (ref "TP29") (pin "1") (pintype "passive"))
      (node (ref "U13") (pin "91") (pinfunction "PIO1_31_91") (pintype "passive"))
    )
    (net (code "63") (name "/PIO0_5-ISP_EN") (class "Default")
      (node (ref "J33") (pin "7") (pintype "passive"))
      (node (ref "J39") (pin "7") (pinfunction "KEY_7") (pintype "passive"))
      (node (ref "R181") (pin "1") (pinfunction "1_1") (pintype "passive"))
    )
    (net (code "64") (name "/PIO0_5-ISP_EN-LED_SWD_ACT") (class "Default")
      (node (ref "R179") (pin "1") (pinfunction "1_1") (pintype "passive"))
      (node (ref "R181") (pin "2") (pinfunction "2_2") (pintype "passive"))
      (node (ref "R182") (pin "1") (pinfunction "1_1") (pintype "passive"))
      (node (ref "U13") (pin "88") (pinfunction "PIO0_5/_TDI_88") (pintype "passive"))
    )
    (net (code "65") (name "/PIO0_10-SWO") (class "Default")
      (node (ref "J33") (pin "6") (pintype "passive"))
      (node (ref "J39") (pin "6") (pinfunction "TDO/SWO_6") (pintype "passive"))
      (node (ref "R176") (pin "1") (pinfunction "1_1") (pintype "passive"))
      (node (ref "U13") (pin "21") (pinfunction "PIO0_10/_ADC0_1_21") (pintype "passive"))
    )
    (net (code "66") (name "/PIO0_11-SWDCLK") (class "Default")
      (node (ref "J33") (pin "4") (pintype "passive"))
      (node (ref "J39") (pin "4") (pinfunction "TCK/SWDCLK_4") (pintype "passive"))
      (node (ref "R183") (pin "2") (pinfunction "2_2") (pintype "passive"))
      (node (ref "U13") (pin "13") (pinfunction "PIO0_11/_ADC0_9_13") (pintype "passive"))
    )
    (net (code "67") (name "/PIO0_12-SWDIO") (class "Default")
      (node (ref "J33") (pin "2") (pintype "passive"))
      (node (ref "J39") (pin "2") (pinfunction "TMS/SWDIO_2") (pintype "passive"))
      (node (ref "R175") (pin "1") (pinfunction "1_1") (pintype "passive"))
      (node (ref "U13") (pin "12") (pinfunction "PIO0_12/_ADC0_10_12") (pintype "passive"))
    )
    (net (code "68") (name "/PMIC_EN") (class "Default")
      (node (ref "R177") (pin "1") (pinfunction "1_1") (pintype "passive"))
    )
    (net (code "69") (name "/TRGT_3v3_DCDC_EN") (class "Default")
      (node (ref "R177") (pin "2") (pinfunction "2_2") (pintype "passive"))
      (node (ref "U13") (pin "26") (pinfunction "PIO0_8_26") (pintype "passive"))
    )
    (net (code "70") (name "/VBAT_DCDC{slash}VBAT_PMU") (class "Default")
      (node (ref "C80") (pin "1") (pinfunction "1_1") (pintype "passive"))
      (node (ref "C81") (pin "1") (pinfunction "1_1") (pintype "passive"))
      (node (ref "C86") (pin "1") (pinfunction "1_1") (pintype "passive"))
      (node (ref "F10") (pin "2") (pinfunction "2_2") (pintype "passive"))
      (node (ref "U13") (pin "49") (pinfunction "VBAT_DCDC_1_49") (pintype "passive"))
      (node (ref "U13") (pin "50") (pinfunction "VBAT_DCDC_2_50") (pintype "passive"))
      (node (ref "U13") (pin "51") (pinfunction "VBAT__PMU_51") (pintype "passive"))
    )
    (net (code "71") (name "/VREF_MCULINK") (class "Default")
      (node (ref "C87") (pin "1") (pinfunction "1_1") (pintype "passive"))
      (node (ref "C88") (pin "1") (pinfunction "1_1") (pintype "passive"))
      (node (ref "R174") (pin "1") (pinfunction "1_1") (pintype "passive"))
      (node (ref "R184") (pin "2") (pinfunction "2_2") (pintype "passive"))
      (node (ref "U13") (pin "17") (pinfunction "VREFP_17") (pintype "passive"))
      (node (ref "U21") (pin "1") (pinfunction "C_1") (pintype "passive"))
    )
    (net (code "77") (name "GND") (class "Default")
      (node (ref "C43") (pin "2") (pinfunction "2_2") (pintype "passive"))
      (node (ref "C44") (pin "2") (pinfunction "2_2") (pintype "passive"))
      (node (ref "C45") (pin "2") (pinfunction "2_2") (pintype "passive"))
      (node (ref "C48") (pin "2") (pinfunction "2_2") (pintype "passive"))
      (node (ref "C49") (pin "2") (pinfunction "2_2") (pintype "passive"))
      (node (ref "C51") (pin "2") (pinfunction "2_2") (pintype "passive"))
      (node (ref "C53") (pin "2") (pinfunction "2_2") (pintype "passive"))
      (node (ref "C56") (pin "2") (pinfunction "2_2") (pintype "passive"))
      (node (ref "C57") (pin "2") (pinfunction "2_2") (pintype "passive"))
      (node (ref "C58") (pin "2") (pinfunction "2_2") (pintype "passive"))
      (node (ref "C59") (pin "2") (pinfunction "2_2") (pintype "passive"))
      (node (ref "C63") (pin "2") (pinfunction "2_2") (pintype "passive"))
      (node (ref "C64") (pin "2") (pinfunction "2_2") (pintype "passive"))
      (node (ref "C65") (pin "2") (pinfunction "2_2") (pintype "passive"))
      (node (ref "C66") (pin "2") (pinfunction "2_2") (pintype "passive"))
      (node (ref "C78") (pin "2") (pinfunction "2_2") (pintype "passive"))
      (node (ref "C79") (pin "2") (pinfunction "2_2") (pintype "passive"))
      (node (ref "C80") (pin "2") (pinfunction "2_2") (pintype "passive"))
      (node (ref "C81") (pin "2") (pinfunction "2_2") (pintype "passive"))
      (node (ref "C86") (pin "2") (pinfunction "2_2") (pintype "passive"))
      (node (ref "C87") (pin "2") (pinfunction "2_2") (pintype "passive"))
      (node (ref "C88") (pin "2") (pinfunction "2_2") (pintype "passive"))
      (node (ref "C89") (pin "2") (pinfunction "2_2") (pintype "passive"))
      (node (ref "C90") (pin "2") (pinfunction "2_2") (pintype "passive"))
      (node (ref "C91") (pin "2") (pinfunction "2_2") (pintype "passive"))
      (node (ref "C92") (pin "2") (pinfunction "2_2") (pintype "passive"))
      (node (ref "J33") (pin "3") (pintype "passive"))
      (node (ref "J33") (pin "5") (pintype "passive"))
      (node (ref "J33") (pin "9") (pintype "passive"))
      (node (ref "J39") (pin "3") (pinfunction "GND_3") (pintype "passive"))
      (node (ref "J39") (pin "5") (pinfunction "GND_5") (pintype "passive"))
      (node (ref "J39") (pin "9") (pinfunction "GND_9") (pintype "passive"))
      (node (ref "R180") (pin "1") (pinfunction "1_1") (pintype "passive"))
      (node (ref "R182") (pin "2") (pinfunction "2_2") (pintype "passive"))
      (node (ref "R183") (pin "1") (pinfunction "1_1") (pintype "passive"))
      (node (ref "R185") (pin "1") (pinfunction "1_1") (pintype "passive"))
      (node (ref "R187") (pin "1") (pinfunction "1_1") (pintype "passive"))
      (node (ref "R188") (pin "1") (pinfunction "1_1") (pintype "passive"))
      (node (ref "R189") (pin "1") (pinfunction "1_1") (pintype "passive"))
      (node (ref "R190") (pin "1") (pinfunction "1_1") (pintype "passive"))
      (node (ref "R191") (pin "1") (pinfunction "1_1") (pintype "passive"))
      (node (ref "R192") (pin "1") (pinfunction "1_1") (pintype "passive"))
      (node (ref "R193") (pin "1") (pinfunction "1_1") (pintype "passive"))
      (node (ref "R194") (pin "1") (pinfunction "1_1") (pintype "passive"))
      (node (ref "R195") (pin "1") (pinfunction "1_1") (pintype "passive"))
      (node (ref "R196") (pin "1") (pinfunction "1_1") (pintype "passive"))
      (node (ref "U13") (pin "101") (pinfunction "EPAD_101") (pintype "passive"))
      (node (ref "U13") (pin "18") (pinfunction "VREFN_18") (pintype "passive"))
      (node (ref "U13") (pin "19") (pinfunction "VSSA_19") (pintype "passive"))
      (node (ref "U13") (pin "46") (pinfunction "VSS_DCDC_1_46") (pintype "passive"))
      (node (ref "U13") (pin "47") (pinfunction "VSS_DCDC_2_47") (pintype "passive"))
      (node (ref "U13") (pin "52") (pinfunction "XTAL32K_P_52") (pintype "passive"))
      (node (ref "U21") (pin "2") (pinfunction "REF_2") (pintype "passive"))
      (node (ref "U21") (pin "3") (pinfunction "A_3") (pintype "passive"))
    )
    (net (code "78") (name "MCU_LINK_3V3") (class "Default")
      (node (ref "C44") (pin "1") (pinfunction "1_1") (pintype "passive"))
      (node (ref "C45") (pin "1") (pinfunction "1_1") (pintype "passive"))
      (node (ref "C48") (pin "1") (pinfunction "1_1") (pintype "passive"))
      (node (ref "C49") (pin "1") (pinfunction "1_1") (pintype "passive"))
      (node (ref "C51") (pin "1") (pinfunction "1_1") (pintype "passive"))
      (node (ref "C53") (pin "1") (pinfunction "1_1") (pintype "passive"))
      (node (ref "C56") (pin "1") (pinfunction "1_1") (pintype "passive"))
      (node (ref "C57") (pin "1") (pinfunction "1_1") (pintype "passive"))
      (node (ref "C58") (pin "1") (pinfunction "1_1") (pintype "passive"))
      (node (ref "C59") (pin "1") (pinfunction "1_1") (pintype "passive"))
      (node (ref "C63") (pin "1") (pinfunction "1_1") (pintype "passive"))
      (node (ref "F7") (pin "2") (pinfunction "2_2") (pintype "passive"))
      (node (ref "U13") (pin "100") (pinfunction "VDD_9_100") (pintype "passive"))
      (node (ref "U13") (pin "15") (pinfunction "VDD_1_15") (pintype "passive"))
      (node (ref "U13") (pin "25") (pinfunction "VDD_2_25") (pintype "passive"))
      (node (ref "U13") (pin "44") (pinfunction "VDD_3_44") (pintype "passive"))
      (node (ref "U13") (pin "63") (pinfunction "VDD_4_63") (pintype "passive"))
      (node (ref "U13") (pin "69") (pinfunction "VDD_5_69") (pintype "passive"))
      (node (ref "U13") (pin "75") (pinfunction "VDD_6_75") (pintype "passive"))
      (node (ref "U13") (pin "84") (pinfunction "VDD_7_84") (pintype "passive"))
      (node (ref "U13") (pin "95") (pinfunction "VDD_8_95") (pintype "passive"))
    )
    (net (code "79") (name "MLINK_3V3") (class "Default")
      (node (ref "C43") (pin "1") (pinfunction "1_1") (pintype "passive"))
      (node (ref "C91") (pin "1") (pinfunction "1_1") (pintype "passive"))
      (node (ref "F10") (pin "1") (pinfunction "1_1") (pintype "passive"))
      (node (ref "F7") (pin "1") (pinfunction "1_1") (pintype "passive"))
      (node (ref "F9") (pin "1") (pinfunction "1_1") (pintype "passive"))
      (node (ref "J33") (pin "1") (pintype "passive"))
      (node (ref "J39") (pin "1") (pinfunction "VCC_1") (pintype "passive"))
      (node (ref "R175") (pin "2") (pinfunction "2_2") (pintype "passive"))
      (node (ref "R176") (pin "2") (pinfunction "2_2") (pintype "passive"))
      (node (ref "R178") (pin "2") (pinfunction "2_2") (pintype "passive"))
      (node (ref "R179") (pin "2") (pinfunction "2_2") (pintype "passive"))
    )
    (net (code "80") (name "Net-(U13C-PIO1_19{slash}_ACMPVREF)") (class "Default")
      (node (ref "R184") (pin "1") (pinfunction "1_1") (pintype "passive"))
      (node (ref "R185") (pin "2") (pinfunction "2_2") (pintype "passive"))
      (node (ref "U13") (pin "58") (pinfunction "PIO1_19/_ACMPVREF_58") (pintype "passive"))
    )
    (net (code "81") (name "VCC_IF_LINK") (class "Default")
      (node (ref "R186") (pin "1") (pinfunction "1_1") (pintype "passive"))
    )
    (net (code "82") (name "unconnected-(J33-Pad8)") (class "Default")
      (node (ref "J33") (pin "8") (pintype "passive+no_connect"))
    )
    (net (code "83") (name "unconnected-(J39-TDI-Pad8)") (class "Default")
      (node (ref "J39") (pin "8") (pinfunction "TDI_8") (pintype "passive+no_connect"))
    )
    (net (code "84") (name "unconnected-(U13A-XTAL32K_N-Pad53)") (class "Default")
      (node (ref "U13") (pin "53") (pinfunction "XTAL32K_N_53") (pintype "passive+no_connect"))
    )
    (net (code "85") (name "unconnected-(U13C-PIO0_6{slash}_TDO-Pad89)") (class "Default")
      (node (ref "U13") (pin "89") (pinfunction "PIO0_6/_TDO_89") (pintype "passive+no_connect"))
    )
    (net (code "86") (name "unconnected-(U13C-PIO0_7-Pad6)") (class "Default")
      (node (ref "U13") (pin "6") (pinfunction "PIO0_7_6") (pintype "passive+no_connect"))
    )
    (net (code "87") (name "unconnected-(U13C-PIO1_0{slash}_ADC0_11-Pad11)") (class "Default")
      (node (ref "U13") (pin "11") (pinfunction "PIO1_0/_ADC0_11_11") (pintype "passive+no_connect"))
    )
    (net (code "88") (name "unconnected-(U13C-PIO1_10-Pad40)") (class "Default")
      (node (ref "U13") (pin "40") (pinfunction "PIO1_10_40") (pintype "passive+no_connect"))
    )
    (net (code "89") (name "unconnected-(U13C-PIO1_11-Pad93)") (class "Default")
      (node (ref "U13") (pin "93") (pinfunction "PIO1_11_93") (pintype "passive+no_connect"))
    )
    (net (code "90") (name "unconnected-(U13C-PIO1_17-Pad43)") (class "Default")
      (node (ref "U13") (pin "43") (pinfunction "PIO1_17_43") (pintype "passive+no_connect"))
    )
    (net (code "91") (name "unconnected-(U13C-PIO1_18{slash}_WAKUP-Pad64)") (class "Default")
      (node (ref "U13") (pin "64") (pinfunction "PIO1_18/_WAKUP_64") (pintype "passive+no_connect"))
    )
  )
)
